# design.net
KiCad netlist of a schematic drawn in EAGLE
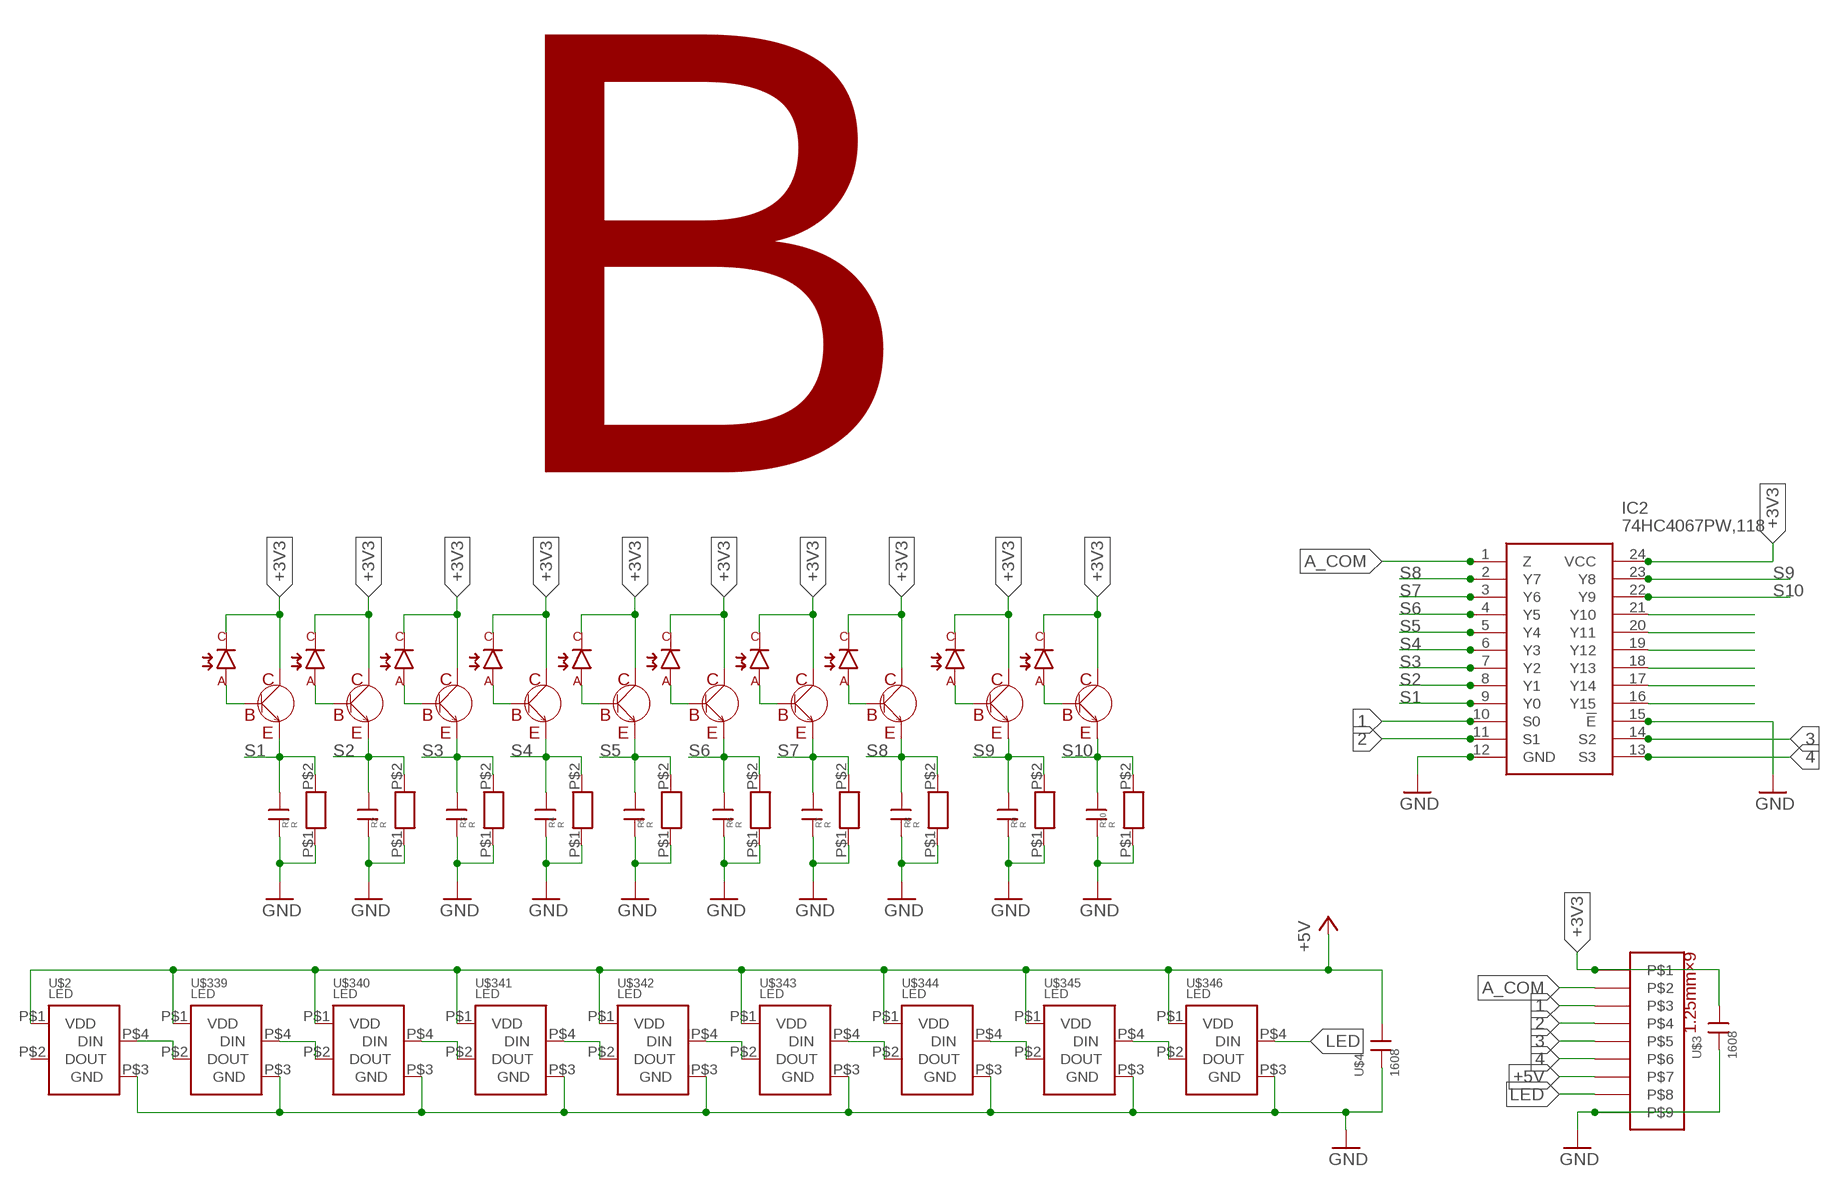
[diagram p0: schematic, sheet 1]

(export (version "E")
  (design (tool "Eeschema 10.0.6"))
  (components
    (comp (ref "C1")
      (value "1608")
      (footprint "eagle-import:CON")
      (libsource (lib "eagle-import") (part "1608"))
    )
    (comp (ref "C2")
      (value "1608")
      (footprint "eagle-import:CON")
      (libsource (lib "eagle-import") (part "1608"))
    )
    (comp (ref "C3")
      (value "1608")
      (footprint "eagle-import:CON")
      (libsource (lib "eagle-import") (part "1608"))
    )
    (comp (ref "C4")
      (value "1608")
      (footprint "eagle-import:CON")
      (libsource (lib "eagle-import") (part "1608"))
    )
    (comp (ref "C5")
      (value "1608")
      (footprint "eagle-import:CON")
      (libsource (lib "eagle-import") (part "1608"))
    )
    (comp (ref "C6")
      (value "1608")
      (footprint "eagle-import:CON")
      (libsource (lib "eagle-import") (part "1608"))
    )
    (comp (ref "C7")
      (value "1608")
      (footprint "eagle-import:CON")
      (libsource (lib "eagle-import") (part "1608"))
    )
    (comp (ref "C8")
      (value "1608")
      (footprint "eagle-import:CON")
      (libsource (lib "eagle-import") (part "1608"))
    )
    (comp (ref "C9")
      (value "1608")
      (footprint "eagle-import:CON")
      (libsource (lib "eagle-import") (part "1608"))
    )
    (comp (ref "C10")
      (value "1608")
      (footprint "eagle-import:CON")
      (libsource (lib "eagle-import") (part "1608"))
    )
    (comp (ref "IC2")
      (value "74HC4067PW,118")
      (footprint "eagle-import:SOP65P640X110-24N")
      (fields (field (name "MOUSER_PART_NUMBER") "771-74HC4067PW-T"))
      (libsource (lib "eagle-import") (part "74HC4067PW,118"))
    )
    (comp (ref "R1") (value "R") (footprint "eagle-import:1608") (libsource (lib "eagle-import") (part "R")))
    (comp (ref "R2") (value "R") (footprint "eagle-import:1608") (libsource (lib "eagle-import") (part "R")))
    (comp (ref "R3") (value "R") (footprint "eagle-import:1608") (libsource (lib "eagle-import") (part "R")))
    (comp (ref "R4") (value "R") (footprint "eagle-import:1608") (libsource (lib "eagle-import") (part "R")))
    (comp (ref "R5") (value "R") (footprint "eagle-import:1608") (libsource (lib "eagle-import") (part "R")))
    (comp (ref "R6") (value "R") (footprint "eagle-import:1608") (libsource (lib "eagle-import") (part "R")))
    (comp (ref "R7") (value "R") (footprint "eagle-import:1608") (libsource (lib "eagle-import") (part "R")))
    (comp (ref "R8") (value "R") (footprint "eagle-import:1608") (libsource (lib "eagle-import") (part "R")))
    (comp (ref "R9") (value "R") (footprint "eagle-import:1608") (libsource (lib "eagle-import") (part "R")))
    (comp (ref "R10") (value "R") (footprint "eagle-import:1608") (libsource (lib "eagle-import") (part "R")))
    (comp (ref "U$1")
      (value "1MMCON")
      (footprint "eagle-import:1MMCON")
      (libsource (lib "eagle-import") (part "1MMCON"))
    )
    (comp (ref "U$2")
      (value "LED")
      (footprint "eagle-import:LED")
      (libsource (lib "eagle-import") (part "LED"))
    )
    (comp (ref "U$3")
      (value "1608")
      (footprint "eagle-import:CON")
      (libsource (lib "eagle-import") (part "1608"))
    )
    (comp (ref "U$4")
      (value "1608")
      (footprint "eagle-import:CON")
      (libsource (lib "eagle-import") (part "1608"))
    )
    (comp (ref "U$33")
      (value "2CS2712")
      (footprint "eagle-import:TRANS_SSM3J325F,LF")
      (libsource (lib "eagle-import") (part "2CS2712"))
    )
    (comp (ref "U$34")
      (value "フォトダイオード")
      (footprint "eagle-import:フォトダイオード")
      (libsource (lib "eagle-import") (part "フォトダイオード"))
    )
    (comp (ref "U$35")
      (value "2CS2712")
      (footprint "eagle-import:TRANS_SSM3J325F,LF")
      (libsource (lib "eagle-import") (part "2CS2712"))
    )
    (comp (ref "U$36")
      (value "フォトダイオード")
      (footprint "eagle-import:フォトダイオード")
      (libsource (lib "eagle-import") (part "フォトダイオード"))
    )
    (comp (ref "U$37")
      (value "2CS2712")
      (footprint "eagle-import:TRANS_SSM3J325F,LF")
      (libsource (lib "eagle-import") (part "2CS2712"))
    )
    (comp (ref "U$38")
      (value "フォトダイオード")
      (footprint "eagle-import:フォトダイオード")
      (libsource (lib "eagle-import") (part "フォトダイオード"))
    )
    (comp (ref "U$39")
      (value "2CS2712")
      (footprint "eagle-import:TRANS_SSM3J325F,LF")
      (libsource (lib "eagle-import") (part "2CS2712"))
    )
    (comp (ref "U$40")
      (value "フォトダイオード")
      (footprint "eagle-import:フォトダイオード")
      (libsource (lib "eagle-import") (part "フォトダイオード"))
    )
    (comp (ref "U$41")
      (value "2CS2712")
      (footprint "eagle-import:TRANS_SSM3J325F,LF")
      (libsource (lib "eagle-import") (part "2CS2712"))
    )
    (comp (ref "U$42")
      (value "フォトダイオード")
      (footprint "eagle-import:フォトダイオード")
      (libsource (lib "eagle-import") (part "フォトダイオード"))
    )
    (comp (ref "U$43")
      (value "2CS2712")
      (footprint "eagle-import:TRANS_SSM3J325F,LF")
      (libsource (lib "eagle-import") (part "2CS2712"))
    )
    (comp (ref "U$44")
      (value "フォトダイオード")
      (footprint "eagle-import:フォトダイオード")
      (libsource (lib "eagle-import") (part "フォトダイオード"))
    )
    (comp (ref "U$45")
      (value "2CS2712")
      (footprint "eagle-import:TRANS_SSM3J325F,LF")
      (libsource (lib "eagle-import") (part "2CS2712"))
    )
    (comp (ref "U$46")
      (value "フォトダイオード")
      (footprint "eagle-import:フォトダイオード")
      (libsource (lib "eagle-import") (part "フォトダイオード"))
    )
    (comp (ref "U$47")
      (value "2CS2712")
      (footprint "eagle-import:TRANS_SSM3J325F,LF")
      (libsource (lib "eagle-import") (part "2CS2712"))
    )
    (comp (ref "U$48")
      (value "フォトダイオード")
      (footprint "eagle-import:フォトダイオード")
      (libsource (lib "eagle-import") (part "フォトダイオード"))
    )
    (comp (ref "U$49")
      (value "2CS2712")
      (footprint "eagle-import:TRANS_SSM3J325F,LF")
      (libsource (lib "eagle-import") (part "2CS2712"))
    )
    (comp (ref "U$50")
      (value "フォトダイオード")
      (footprint "eagle-import:フォトダイオード")
      (libsource (lib "eagle-import") (part "フォトダイオード"))
    )
    (comp (ref "U$51")
      (value "2CS2712")
      (footprint "eagle-import:TRANS_SSM3J325F,LF")
      (libsource (lib "eagle-import") (part "2CS2712"))
    )
    (comp (ref "U$52")
      (value "フォトダイオード")
      (footprint "eagle-import:フォトダイオード")
      (libsource (lib "eagle-import") (part "フォトダイオード"))
    )
    (comp (ref "U$339")
      (value "LED")
      (footprint "eagle-import:LED")
      (libsource (lib "eagle-import") (part "LED"))
    )
    (comp (ref "U$340")
      (value "LED")
      (footprint "eagle-import:LED")
      (libsource (lib "eagle-import") (part "LED"))
    )
    (comp (ref "U$341")
      (value "LED")
      (footprint "eagle-import:LED")
      (libsource (lib "eagle-import") (part "LED"))
    )
    (comp (ref "U$342")
      (value "LED")
      (footprint "eagle-import:LED")
      (libsource (lib "eagle-import") (part "LED"))
    )
    (comp (ref "U$343")
      (value "LED")
      (footprint "eagle-import:LED")
      (libsource (lib "eagle-import") (part "LED"))
    )
    (comp (ref "U$344")
      (value "LED")
      (footprint "eagle-import:LED")
      (libsource (lib "eagle-import") (part "LED"))
    )
    (comp (ref "U$345")
      (value "LED")
      (footprint "eagle-import:LED")
      (libsource (lib "eagle-import") (part "LED"))
    )
    (comp (ref "U$346")
      (value "LED")
      (footprint "eagle-import:LED")
      (libsource (lib "eagle-import") (part "LED"))
    )
  )
  (nets
    (net (code "1") (name "+3V3") (class "Default")
      (node (ref "IC2") (pin "24") (pinfunction "VCC_24") (pintype "bidirectional"))
      (node (ref "U$1") (pin "P$1") (pinfunction "P$1_P$1") (pintype "bidirectional"))
      (node (ref "U$3") (pin "P$1") (pinfunction "1_P$1") (pintype "bidirectional"))
      (node (ref "U$33") (pin "C") (pinfunction "C_C") (pintype "bidirectional"))
      (node (ref "U$34") (pin "C") (pinfunction "C_C") (pintype "bidirectional"))
      (node (ref "U$35") (pin "C") (pinfunction "C_C") (pintype "bidirectional"))
      (node (ref "U$36") (pin "C") (pinfunction "C_C") (pintype "bidirectional"))
      (node (ref "U$37") (pin "C") (pinfunction "C_C") (pintype "bidirectional"))
      (node (ref "U$38") (pin "C") (pinfunction "C_C") (pintype "bidirectional"))
      (node (ref "U$39") (pin "C") (pinfunction "C_C") (pintype "bidirectional"))
      (node (ref "U$40") (pin "C") (pinfunction "C_C") (pintype "bidirectional"))
      (node (ref "U$41") (pin "C") (pinfunction "C_C") (pintype "bidirectional"))
      (node (ref "U$42") (pin "C") (pinfunction "C_C") (pintype "bidirectional"))
      (node (ref "U$43") (pin "C") (pinfunction "C_C") (pintype "bidirectional"))
      (node (ref "U$44") (pin "C") (pinfunction "C_C") (pintype "bidirectional"))
      (node (ref "U$45") (pin "C") (pinfunction "C_C") (pintype "bidirectional"))
      (node (ref "U$46") (pin "C") (pinfunction "C_C") (pintype "bidirectional"))
      (node (ref "U$47") (pin "C") (pinfunction "C_C") (pintype "bidirectional"))
      (node (ref "U$48") (pin "C") (pinfunction "C_C") (pintype "bidirectional"))
      (node (ref "U$49") (pin "C") (pinfunction "C_C") (pintype "bidirectional"))
      (node (ref "U$50") (pin "C") (pinfunction "C_C") (pintype "bidirectional"))
      (node (ref "U$51") (pin "C") (pinfunction "C_C") (pintype "bidirectional"))
      (node (ref "U$52") (pin "C") (pinfunction "C_C") (pintype "bidirectional"))
    )
    (net (code "2") (name "+5V") (class "Default")
      (node (ref "U$1") (pin "P$7") (pinfunction "P$7_P$7") (pintype "bidirectional"))
      (node (ref "U$2") (pin "P$1") (pinfunction "VDD_P$1") (pintype "bidirectional"))
      (node (ref "U$339") (pin "P$1") (pinfunction "VDD_P$1") (pintype "bidirectional"))
      (node (ref "U$340") (pin "P$1") (pinfunction "VDD_P$1") (pintype "bidirectional"))
      (node (ref "U$341") (pin "P$1") (pinfunction "VDD_P$1") (pintype "bidirectional"))
      (node (ref "U$342") (pin "P$1") (pinfunction "VDD_P$1") (pintype "bidirectional"))
      (node (ref "U$343") (pin "P$1") (pinfunction "VDD_P$1") (pintype "bidirectional"))
      (node (ref "U$344") (pin "P$1") (pinfunction "VDD_P$1") (pintype "bidirectional"))
      (node (ref "U$345") (pin "P$1") (pinfunction "VDD_P$1") (pintype "bidirectional"))
      (node (ref "U$346") (pin "P$1") (pinfunction "VDD_P$1") (pintype "bidirectional"))
      (node (ref "U$4") (pin "P$1") (pinfunction "1_P$1") (pintype "bidirectional"))
    )
    (net (code "3") (name "/S1") (class "Default")
      (node (ref "C1") (pin "P$1") (pinfunction "1_P$1") (pintype "bidirectional"))
      (node (ref "IC2") (pin "9") (pinfunction "Y0_9") (pintype "bidirectional"))
      (node (ref "R1") (pin "P$2") (pinfunction "P$2_P$2") (pintype "bidirectional"))
      (node (ref "U$33") (pin "E") (pinfunction "E_E") (pintype "bidirectional"))
    )
    (net (code "4") (name "/S2") (class "Default")
      (node (ref "C2") (pin "P$1") (pinfunction "1_P$1") (pintype "bidirectional"))
      (node (ref "IC2") (pin "8") (pinfunction "Y1_8") (pintype "bidirectional"))
      (node (ref "R2") (pin "P$2") (pinfunction "P$2_P$2") (pintype "bidirectional"))
      (node (ref "U$35") (pin "E") (pinfunction "E_E") (pintype "bidirectional"))
    )
    (net (code "5") (name "/S3") (class "Default")
      (node (ref "C3") (pin "P$1") (pinfunction "1_P$1") (pintype "bidirectional"))
      (node (ref "IC2") (pin "7") (pinfunction "Y2_7") (pintype "bidirectional"))
      (node (ref "R3") (pin "P$2") (pinfunction "P$2_P$2") (pintype "bidirectional"))
      (node (ref "U$37") (pin "E") (pinfunction "E_E") (pintype "bidirectional"))
    )
    (net (code "6") (name "/S4") (class "Default")
      (node (ref "C4") (pin "P$1") (pinfunction "1_P$1") (pintype "bidirectional"))
      (node (ref "IC2") (pin "6") (pinfunction "Y3_6") (pintype "bidirectional"))
      (node (ref "R4") (pin "P$2") (pinfunction "P$2_P$2") (pintype "bidirectional"))
      (node (ref "U$39") (pin "E") (pinfunction "E_E") (pintype "bidirectional"))
    )
    (net (code "7") (name "/S5") (class "Default")
      (node (ref "C5") (pin "P$1") (pinfunction "1_P$1") (pintype "bidirectional"))
      (node (ref "IC2") (pin "5") (pinfunction "Y4_5") (pintype "bidirectional"))
      (node (ref "R5") (pin "P$2") (pinfunction "P$2_P$2") (pintype "bidirectional"))
      (node (ref "U$41") (pin "E") (pinfunction "E_E") (pintype "bidirectional"))
    )
    (net (code "8") (name "/S6") (class "Default")
      (node (ref "C6") (pin "P$1") (pinfunction "1_P$1") (pintype "bidirectional"))
      (node (ref "IC2") (pin "4") (pinfunction "Y5_4") (pintype "bidirectional"))
      (node (ref "R6") (pin "P$2") (pinfunction "P$2_P$2") (pintype "bidirectional"))
      (node (ref "U$43") (pin "E") (pinfunction "E_E") (pintype "bidirectional"))
    )
    (net (code "9") (name "/S7") (class "Default")
      (node (ref "C7") (pin "P$1") (pinfunction "1_P$1") (pintype "bidirectional"))
      (node (ref "IC2") (pin "3") (pinfunction "Y6_3") (pintype "bidirectional"))
      (node (ref "R7") (pin "P$2") (pinfunction "P$2_P$2") (pintype "bidirectional"))
      (node (ref "U$45") (pin "E") (pinfunction "E_E") (pintype "bidirectional"))
    )
    (net (code "10") (name "/S8") (class "Default")
      (node (ref "C8") (pin "P$1") (pinfunction "1_P$1") (pintype "bidirectional"))
      (node (ref "IC2") (pin "2") (pinfunction "Y7_2") (pintype "bidirectional"))
      (node (ref "R8") (pin "P$2") (pinfunction "P$2_P$2") (pintype "bidirectional"))
      (node (ref "U$47") (pin "E") (pinfunction "E_E") (pintype "bidirectional"))
    )
    (net (code "11") (name "/S9") (class "Default")
      (node (ref "C9") (pin "P$1") (pinfunction "1_P$1") (pintype "bidirectional"))
      (node (ref "IC2") (pin "23") (pinfunction "Y8_23") (pintype "bidirectional"))
      (node (ref "R9") (pin "P$2") (pinfunction "P$2_P$2") (pintype "bidirectional"))
      (node (ref "U$49") (pin "E") (pinfunction "E_E") (pintype "bidirectional"))
    )
    (net (code "12") (name "/S10") (class "Default")
      (node (ref "C10") (pin "P$1") (pinfunction "1_P$1") (pintype "bidirectional"))
      (node (ref "IC2") (pin "22") (pinfunction "Y9_22") (pintype "bidirectional"))
      (node (ref "R10") (pin "P$2") (pinfunction "P$2_P$2") (pintype "bidirectional"))
      (node (ref "U$51") (pin "E") (pinfunction "E_E") (pintype "bidirectional"))
    )
    (net (code "13") (name "1") (class "Default")
      (node (ref "IC2") (pin "10") (pinfunction "S0_10") (pintype "bidirectional"))
      (node (ref "U$1") (pin "P$3") (pinfunction "P$3_P$3") (pintype "bidirectional"))
    )
    (net (code "14") (name "2") (class "Default")
      (node (ref "IC2") (pin "11") (pinfunction "S1_11") (pintype "bidirectional"))
      (node (ref "U$1") (pin "P$4") (pinfunction "P$4_P$4") (pintype "bidirectional"))
    )
    (net (code "15") (name "3") (class "Default")
      (node (ref "IC2") (pin "14") (pinfunction "S2_14") (pintype "bidirectional"))
      (node (ref "U$1") (pin "P$5") (pinfunction "P$5_P$5") (pintype "bidirectional"))
    )
    (net (code "16") (name "4") (class "Default")
      (node (ref "IC2") (pin "13") (pinfunction "S3_13") (pintype "bidirectional"))
      (node (ref "U$1") (pin "P$6") (pinfunction "P$6_P$6") (pintype "bidirectional"))
    )
    (net (code "17") (name "A_COM") (class "Default")
      (node (ref "IC2") (pin "1") (pinfunction "Z_1") (pintype "bidirectional"))
      (node (ref "U$1") (pin "P$2") (pinfunction "P$2_P$2") (pintype "bidirectional"))
    )
    (net (code "18") (name "GND") (class "Default")
      (node (ref "C1") (pin "P$2") (pinfunction "2_P$2") (pintype "bidirectional"))
      (node (ref "C10") (pin "P$2") (pinfunction "2_P$2") (pintype "bidirectional"))
      (node (ref "C2") (pin "P$2") (pinfunction "2_P$2") (pintype "bidirectional"))
      (node (ref "C3") (pin "P$2") (pinfunction "2_P$2") (pintype "bidirectional"))
      (node (ref "C4") (pin "P$2") (pinfunction "2_P$2") (pintype "bidirectional"))
      (node (ref "C5") (pin "P$2") (pinfunction "2_P$2") (pintype "bidirectional"))
      (node (ref "C6") (pin "P$2") (pinfunction "2_P$2") (pintype "bidirectional"))
      (node (ref "C7") (pin "P$2") (pinfunction "2_P$2") (pintype "bidirectional"))
      (node (ref "C8") (pin "P$2") (pinfunction "2_P$2") (pintype "bidirectional"))
      (node (ref "C9") (pin "P$2") (pinfunction "2_P$2") (pintype "bidirectional"))
      (node (ref "IC2") (pin "12") (pinfunction "GND_12") (pintype "bidirectional"))
      (node (ref "IC2") (pin "15") (pinfunction "~{E}_15") (pintype "bidirectional"))
      (node (ref "R1") (pin "P$1") (pinfunction "P$1_P$1") (pintype "bidirectional"))
      (node (ref "R10") (pin "P$1") (pinfunction "P$1_P$1") (pintype "bidirectional"))
      (node (ref "R2") (pin "P$1") (pinfunction "P$1_P$1") (pintype "bidirectional"))
      (node (ref "R3") (pin "P$1") (pinfunction "P$1_P$1") (pintype "bidirectional"))
      (node (ref "R4") (pin "P$1") (pinfunction "P$1_P$1") (pintype "bidirectional"))
      (node (ref "R5") (pin "P$1") (pinfunction "P$1_P$1") (pintype "bidirectional"))
      (node (ref "R6") (pin "P$1") (pinfunction "P$1_P$1") (pintype "bidirectional"))
      (node (ref "R7") (pin "P$1") (pinfunction "P$1_P$1") (pintype "bidirectional"))
      (node (ref "R8") (pin "P$1") (pinfunction "P$1_P$1") (pintype "bidirectional"))
      (node (ref "R9") (pin "P$1") (pinfunction "P$1_P$1") (pintype "bidirectional"))
      (node (ref "U$1") (pin "P$9") (pinfunction "P$9_P$9") (pintype "bidirectional"))
      (node (ref "U$2") (pin "P$3") (pinfunction "GND_P$3") (pintype "bidirectional"))
      (node (ref "U$3") (pin "P$2") (pinfunction "2_P$2") (pintype "bidirectional"))
      (node (ref "U$339") (pin "P$3") (pinfunction "GND_P$3") (pintype "bidirectional"))
      (node (ref "U$340") (pin "P$3") (pinfunction "GND_P$3") (pintype "bidirectional"))
      (node (ref "U$341") (pin "P$3") (pinfunction "GND_P$3") (pintype "bidirectional"))
      (node (ref "U$342") (pin "P$3") (pinfunction "GND_P$3") (pintype "bidirectional"))
      (node (ref "U$343") (pin "P$3") (pinfunction "GND_P$3") (pintype "bidirectional"))
      (node (ref "U$344") (pin "P$3") (pinfunction "GND_P$3") (pintype "bidirectional"))
      (node (ref "U$345") (pin "P$3") (pinfunction "GND_P$3") (pintype "bidirectional"))
      (node (ref "U$346") (pin "P$3") (pinfunction "GND_P$3") (pintype "bidirectional"))
      (node (ref "U$4") (pin "P$2") (pinfunction "2_P$2") (pintype "bidirectional"))
    )
    (net (code "19") (name "LED") (class "Default")
      (node (ref "U$1") (pin "P$8") (pinfunction "P$8_P$8") (pintype "bidirectional"))
      (node (ref "U$346") (pin "P$4") (pinfunction "DIN_P$4") (pintype "bidirectional"))
    )
    (net (code "20") (name "Net-(U$2-DIN)") (class "Default")
      (node (ref "U$2") (pin "P$4") (pinfunction "DIN_P$4") (pintype "bidirectional"))
      (node (ref "U$339") (pin "P$2") (pinfunction "DOUT_P$2") (pintype "bidirectional"))
    )
    (net (code "21") (name "Net-(U$33-PadB)") (class "Default")
      (node (ref "U$33") (pin "B") (pinfunction "B_B") (pintype "bidirectional"))
      (node (ref "U$34") (pin "A") (pinfunction "A_A") (pintype "bidirectional"))
    )
    (net (code "22") (name "Net-(U$35-PadB)") (class "Default")
      (node (ref "U$35") (pin "B") (pinfunction "B_B") (pintype "bidirectional"))
      (node (ref "U$36") (pin "A") (pinfunction "A_A") (pintype "bidirectional"))
    )
    (net (code "23") (name "Net-(U$37-PadB)") (class "Default")
      (node (ref "U$37") (pin "B") (pinfunction "B_B") (pintype "bidirectional"))
      (node (ref "U$38") (pin "A") (pinfunction "A_A") (pintype "bidirectional"))
    )
    (net (code "24") (name "Net-(U$39-PadB)") (class "Default")
      (node (ref "U$39") (pin "B") (pinfunction "B_B") (pintype "bidirectional"))
      (node (ref "U$40") (pin "A") (pinfunction "A_A") (pintype "bidirectional"))
    )
    (net (code "25") (name "Net-(U$41-PadB)") (class "Default")
      (node (ref "U$41") (pin "B") (pinfunction "B_B") (pintype "bidirectional"))
      (node (ref "U$42") (pin "A") (pinfunction "A_A") (pintype "bidirectional"))
    )
    (net (code "26") (name "Net-(U$43-PadB)") (class "Default")
      (node (ref "U$43") (pin "B") (pinfunction "B_B") (pintype "bidirectional"))
      (node (ref "U$44") (pin "A") (pinfunction "A_A") (pintype "bidirectional"))
    )
    (net (code "27") (name "Net-(U$45-PadB)") (class "Default")
      (node (ref "U$45") (pin "B") (pinfunction "B_B") (pintype "bidirectional"))
      (node (ref "U$46") (pin "A") (pinfunction "A_A") (pintype "bidirectional"))
    )
    (net (code "28") (name "Net-(U$47-PadB)") (class "Default")
      (node (ref "U$47") (pin "B") (pinfunction "B_B") (pintype "bidirectional"))
      (node (ref "U$48") (pin "A") (pinfunction "A_A") (pintype "bidirectional"))
    )
    (net (code "29") (name "Net-(U$49-PadB)") (class "Default")
      (node (ref "U$49") (pin "B") (pinfunction "B_B") (pintype "bidirectional"))
      (node (ref "U$50") (pin "A") (pinfunction "A_A") (pintype "bidirectional"))
    )
    (net (code "30") (name "Net-(U$51-PadB)") (class "Default")
      (node (ref "U$51") (pin "B") (pinfunction "B_B") (pintype "bidirectional"))
      (node (ref "U$52") (pin "A") (pinfunction "A_A") (pintype "bidirectional"))
    )
    (net (code "31") (name "Net-(U$339-DIN)") (class "Default")
      (node (ref "U$339") (pin "P$4") (pinfunction "DIN_P$4") (pintype "bidirectional"))
      (node (ref "U$340") (pin "P$2") (pinfunction "DOUT_P$2") (pintype "bidirectional"))
    )
    (net (code "32") (name "Net-(U$340-DIN)") (class "Default")
      (node (ref "U$340") (pin "P$4") (pinfunction "DIN_P$4") (pintype "bidirectional"))
      (node (ref "U$341") (pin "P$2") (pinfunction "DOUT_P$2") (pintype "bidirectional"))
    )
    (net (code "33") (name "Net-(U$341-DIN)") (class "Default")
      (node (ref "U$341") (pin "P$4") (pinfunction "DIN_P$4") (pintype "bidirectional"))
      (node (ref "U$342") (pin "P$2") (pinfunction "DOUT_P$2") (pintype "bidirectional"))
    )
    (net (code "34") (name "Net-(U$342-DIN)") (class "Default")
      (node (ref "U$342") (pin "P$4") (pinfunction "DIN_P$4") (pintype "bidirectional"))
      (node (ref "U$343") (pin "P$2") (pinfunction "DOUT_P$2") (pintype "bidirectional"))
    )
    (net (code "35") (name "Net-(U$343-DIN)") (class "Default")
      (node (ref "U$343") (pin "P$4") (pinfunction "DIN_P$4") (pintype "bidirectional"))
      (node (ref "U$344") (pin "P$2") (pinfunction "DOUT_P$2") (pintype "bidirectional"))
    )
    (net (code "36") (name "Net-(U$344-DIN)") (class "Default")
      (node (ref "U$344") (pin "P$4") (pinfunction "DIN_P$4") (pintype "bidirectional"))
      (node (ref "U$345") (pin "P$2") (pinfunction "DOUT_P$2") (pintype "bidirectional"))
    )
    (net (code "37") (name "Net-(U$345-DIN)") (class "Default")
      (node (ref "U$345") (pin "P$4") (pinfunction "DIN_P$4") (pintype "bidirectional"))
      (node (ref "U$346") (pin "P$2") (pinfunction "DOUT_P$2") (pintype "bidirectional"))
    )
    (net (code "38") (name "unconnected-(IC2-Y10-Pad21)") (class "Default")
      (node (ref "IC2") (pin "21") (pinfunction "Y10_21") (pintype "bidirectional"))
    )
    (net (code "39") (name "unconnected-(IC2-Y11-Pad20)") (class "Default")
      (node (ref "IC2") (pin "20") (pinfunction "Y11_20") (pintype "bidirectional"))
    )
    (net (code "40") (name "unconnected-(IC2-Y12-Pad19)") (class "Default")
      (node (ref "IC2") (pin "19") (pinfunction "Y12_19") (pintype "bidirectional"))
    )
    (net (code "41") (name "unconnected-(IC2-Y13-Pad18)") (class "Default")
      (node (ref "IC2") (pin "18") (pinfunction "Y13_18") (pintype "bidirectional"))
    )
    (net (code "42") (name "unconnected-(IC2-Y14-Pad17)") (class "Default")
      (node (ref "IC2") (pin "17") (pinfunction "Y14_17") (pintype "bidirectional"))
    )
    (net (code "43") (name "unconnected-(IC2-Y15-Pad16)") (class "Default")
      (node (ref "IC2") (pin "16") (pinfunction "Y15_16") (pintype "bidirectional"))
    )
    (net (code "44") (name "unconnected-(U$2-DOUT-PadP$2)") (class "Default")
      (node (ref "U$2") (pin "P$2") (pinfunction "DOUT_P$2") (pintype "bidirectional"))
    )
  )
)
